# Clock2Smaller.net
KiCad netlist of a schematic drawn in EAGLE
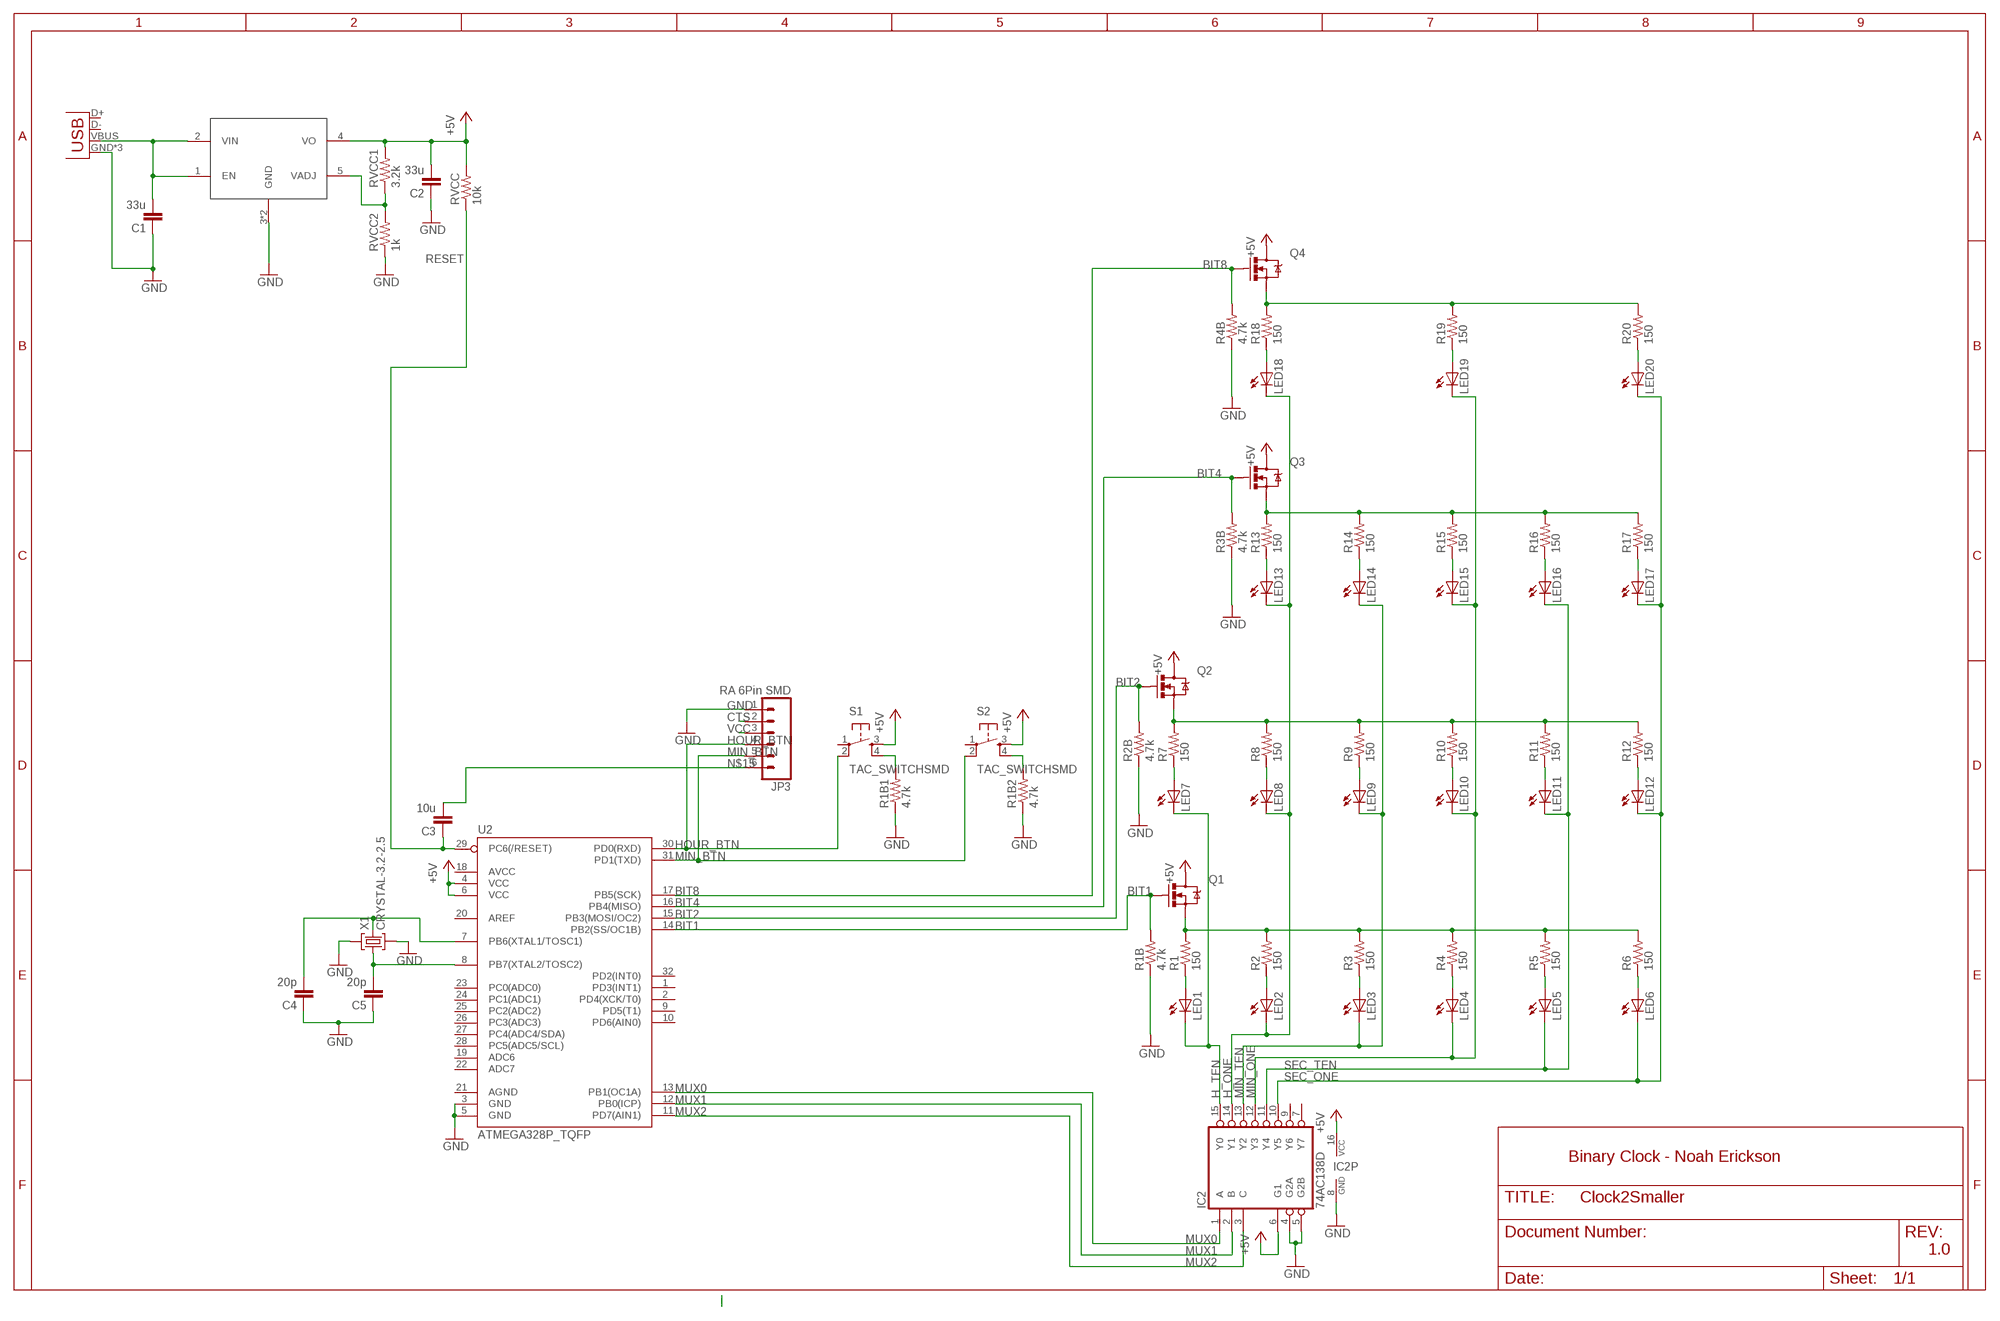
[diagram p0: schematic, sheet 1]

(export (version "E")
  (design (tool "Eeschema 10.0.6"))
  (components
    (comp (ref "C1")
      (value "33u")
      (footprint "eagle-import:C0805")
      (libsource (lib "eagle-import") (part "C-EUC0805"))
    )
    (comp (ref "C2")
      (value "33u")
      (footprint "eagle-import:C0805")
      (libsource (lib "eagle-import") (part "C-EUC0805"))
    )
    (comp (ref "C3")
      (value "10u")
      (footprint "eagle-import:C0805")
      (libsource (lib "eagle-import") (part "C-EUC0805"))
    )
    (comp (ref "C4")
      (value "20p")
      (footprint "eagle-import:C0805")
      (libsource (lib "eagle-import") (part "C-EUC0805"))
    )
    (comp (ref "C5")
      (value "20p")
      (footprint "eagle-import:C0805")
      (libsource (lib "eagle-import") (part "C-EUC0805"))
    )
    (comp (ref "IC2")
      (value "74AC138D")
      (footprint "eagle-import:SO16")
      (libsource (lib "eagle-import") (part "74138DAC"))
    )
    (comp (ref "JP1")
      (value "USB-MICROB")
      (footprint "eagle-import:USB-MICROB")
      (libsource (lib "eagle-import") (part "USB-MICROB"))
    )
    (comp (ref "JP3")
      (value "RA 6Pin SMD")
      (footprint "eagle-import:1X06-SMD")
      (libsource (lib "eagle-import") (part "M06SMD"))
    )
    (comp (ref "LED1")
      (value "LEDSML0805")
      (footprint "eagle-import:SML0805")
      (libsource (lib "eagle-import") (part "LEDSML0805"))
    )
    (comp (ref "LED2")
      (value "LEDSML0805")
      (footprint "eagle-import:SML0805")
      (libsource (lib "eagle-import") (part "LEDSML0805"))
    )
    (comp (ref "LED3")
      (value "LEDSML0805")
      (footprint "eagle-import:SML0805")
      (libsource (lib "eagle-import") (part "LEDSML0805"))
    )
    (comp (ref "LED4")
      (value "LEDSML0805")
      (footprint "eagle-import:SML0805")
      (libsource (lib "eagle-import") (part "LEDSML0805"))
    )
    (comp (ref "LED5")
      (value "LEDSML0805")
      (footprint "eagle-import:SML0805")
      (libsource (lib "eagle-import") (part "LEDSML0805"))
    )
    (comp (ref "LED6")
      (value "LEDSML0805")
      (footprint "eagle-import:SML0805")
      (libsource (lib "eagle-import") (part "LEDSML0805"))
    )
    (comp (ref "LED7")
      (value "LEDSML0805")
      (footprint "eagle-import:SML0805")
      (libsource (lib "eagle-import") (part "LEDSML0805"))
    )
    (comp (ref "LED8")
      (value "LEDSML0805")
      (footprint "eagle-import:SML0805")
      (libsource (lib "eagle-import") (part "LEDSML0805"))
    )
    (comp (ref "LED9")
      (value "LEDSML0805")
      (footprint "eagle-import:SML0805")
      (libsource (lib "eagle-import") (part "LEDSML0805"))
    )
    (comp (ref "LED10")
      (value "LEDSML0805")
      (footprint "eagle-import:SML0805")
      (libsource (lib "eagle-import") (part "LEDSML0805"))
    )
    (comp (ref "LED11")
      (value "LEDSML0805")
      (footprint "eagle-import:SML0805")
      (libsource (lib "eagle-import") (part "LEDSML0805"))
    )
    (comp (ref "LED12")
      (value "LEDSML0805")
      (footprint "eagle-import:SML0805")
      (libsource (lib "eagle-import") (part "LEDSML0805"))
    )
    (comp (ref "LED13")
      (value "LEDSML0805")
      (footprint "eagle-import:SML0805")
      (libsource (lib "eagle-import") (part "LEDSML0805"))
    )
    (comp (ref "LED14")
      (value "LEDSML0805")
      (footprint "eagle-import:SML0805")
      (libsource (lib "eagle-import") (part "LEDSML0805"))
    )
    (comp (ref "LED15")
      (value "LEDSML0805")
      (footprint "eagle-import:SML0805")
      (libsource (lib "eagle-import") (part "LEDSML0805"))
    )
    (comp (ref "LED16")
      (value "LEDSML0805")
      (footprint "eagle-import:SML0805")
      (libsource (lib "eagle-import") (part "LEDSML0805"))
    )
    (comp (ref "LED17")
      (value "LEDSML0805")
      (footprint "eagle-import:SML0805")
      (libsource (lib "eagle-import") (part "LEDSML0805"))
    )
    (comp (ref "LED18")
      (value "LEDSML0805")
      (footprint "eagle-import:SML0805")
      (libsource (lib "eagle-import") (part "LEDSML0805"))
    )
    (comp (ref "LED19")
      (value "LEDSML0805")
      (footprint "eagle-import:SML0805")
      (libsource (lib "eagle-import") (part "LEDSML0805"))
    )
    (comp (ref "LED20")
      (value "LEDSML0805")
      (footprint "eagle-import:SML0805")
      (libsource (lib "eagle-import") (part "LEDSML0805"))
    )
    (comp (ref "Q1")
      (value "MOSFET-NCHANNELBSS138")
      (footprint "eagle-import:SOT23-3")
      (libsource (lib "eagle-import") (part "MOSFET-NCHANNELBSS138"))
    )
    (comp (ref "Q2")
      (value "MOSFET-NCHANNELBSS138")
      (footprint "eagle-import:SOT23-3")
      (libsource (lib "eagle-import") (part "MOSFET-NCHANNELBSS138"))
    )
    (comp (ref "Q3")
      (value "MOSFET-NCHANNELBSS138")
      (footprint "eagle-import:SOT23-3")
      (libsource (lib "eagle-import") (part "MOSFET-NCHANNELBSS138"))
    )
    (comp (ref "Q4")
      (value "MOSFET-NCHANNELBSS138")
      (footprint "eagle-import:SOT23-3")
      (libsource (lib "eagle-import") (part "MOSFET-NCHANNELBSS138"))
    )
    (comp (ref "R1")
      (value "150")
      (footprint "eagle-import:R0805")
      (libsource (lib "eagle-import") (part "R-US_R0805"))
    )
    (comp (ref "R1B")
      (value "4.7k")
      (footprint "eagle-import:R0805")
      (libsource (lib "eagle-import") (part "R-US_R0805"))
    )
    (comp (ref "R1B1")
      (value "4.7k")
      (footprint "eagle-import:R0805")
      (libsource (lib "eagle-import") (part "R-US_R0805"))
    )
    (comp (ref "R1B2")
      (value "4.7k")
      (footprint "eagle-import:R0805")
      (libsource (lib "eagle-import") (part "R-US_R0805"))
    )
    (comp (ref "R2")
      (value "150")
      (footprint "eagle-import:R0805")
      (libsource (lib "eagle-import") (part "R-US_R0805"))
    )
    (comp (ref "R2B")
      (value "4.7k")
      (footprint "eagle-import:R0805")
      (libsource (lib "eagle-import") (part "R-US_R0805"))
    )
    (comp (ref "R3")
      (value "150")
      (footprint "eagle-import:R0805")
      (libsource (lib "eagle-import") (part "R-US_R0805"))
    )
    (comp (ref "R3B")
      (value "4.7k")
      (footprint "eagle-import:R0805")
      (libsource (lib "eagle-import") (part "R-US_R0805"))
    )
    (comp (ref "R4")
      (value "150")
      (footprint "eagle-import:R0805")
      (libsource (lib "eagle-import") (part "R-US_R0805"))
    )
    (comp (ref "R4B")
      (value "4.7k")
      (footprint "eagle-import:R0805")
      (libsource (lib "eagle-import") (part "R-US_R0805"))
    )
    (comp (ref "R5")
      (value "150")
      (footprint "eagle-import:R0805")
      (libsource (lib "eagle-import") (part "R-US_R0805"))
    )
    (comp (ref "R6")
      (value "150")
      (footprint "eagle-import:R0805")
      (libsource (lib "eagle-import") (part "R-US_R0805"))
    )
    (comp (ref "R7")
      (value "150")
      (footprint "eagle-import:R0805")
      (libsource (lib "eagle-import") (part "R-US_R0805"))
    )
    (comp (ref "R8")
      (value "150")
      (footprint "eagle-import:R0805")
      (libsource (lib "eagle-import") (part "R-US_R0805"))
    )
    (comp (ref "R9")
      (value "150")
      (footprint "eagle-import:R0805")
      (libsource (lib "eagle-import") (part "R-US_R0805"))
    )
    (comp (ref "R10")
      (value "150")
      (footprint "eagle-import:R0805")
      (libsource (lib "eagle-import") (part "R-US_R0805"))
    )
    (comp (ref "R11")
      (value "150")
      (footprint "eagle-import:R0805")
      (libsource (lib "eagle-import") (part "R-US_R0805"))
    )
    (comp (ref "R12")
      (value "150")
      (footprint "eagle-import:R0805")
      (libsource (lib "eagle-import") (part "R-US_R0805"))
    )
    (comp (ref "R13")
      (value "150")
      (footprint "eagle-import:R0805")
      (libsource (lib "eagle-import") (part "R-US_R0805"))
    )
    (comp (ref "R14")
      (value "150")
      (footprint "eagle-import:R0805")
      (libsource (lib "eagle-import") (part "R-US_R0805"))
    )
    (comp (ref "R15")
      (value "150")
      (footprint "eagle-import:R0805")
      (libsource (lib "eagle-import") (part "R-US_R0805"))
    )
    (comp (ref "R16")
      (value "150")
      (footprint "eagle-import:R0805")
      (libsource (lib "eagle-import") (part "R-US_R0805"))
    )
    (comp (ref "R17")
      (value "150")
      (footprint "eagle-import:R0805")
      (libsource (lib "eagle-import") (part "R-US_R0805"))
    )
    (comp (ref "R18")
      (value "150")
      (footprint "eagle-import:R0805")
      (libsource (lib "eagle-import") (part "R-US_R0805"))
    )
    (comp (ref "R19")
      (value "150")
      (footprint "eagle-import:R0805")
      (libsource (lib "eagle-import") (part "R-US_R0805"))
    )
    (comp (ref "R20")
      (value "150")
      (footprint "eagle-import:R0805")
      (libsource (lib "eagle-import") (part "R-US_R0805"))
    )
    (comp (ref "RVCC")
      (value "10k")
      (footprint "eagle-import:R0805")
      (libsource (lib "eagle-import") (part "R-US_R0805"))
    )
    (comp (ref "RVCC1")
      (value "3.2k")
      (footprint "eagle-import:R0805")
      (libsource (lib "eagle-import") (part "R-US_R0805"))
    )
    (comp (ref "RVCC2")
      (value "1k")
      (footprint "eagle-import:R0805")
      (libsource (lib "eagle-import") (part "R-US_R0805"))
    )
    (comp (ref "S1")
      (value "TAC_SWITCHSMD")
      (footprint "eagle-import:TACTILE-SWITCH-SMD")
      (libsource (lib "eagle-import") (part "TAC_SWITCHSMD"))
    )
    (comp (ref "S2")
      (value "TAC_SWITCHSMD")
      (footprint "eagle-import:TACTILE-SWITCH-SMD")
      (libsource (lib "eagle-import") (part "TAC_SWITCHSMD"))
    )
    (comp (ref "U$1")
      (value "TLF1963")
      (footprint "eagle-import:DPAK")
      (libsource (lib "eagle-import") (part "TLF1963"))
    )
    (comp (ref "U2")
      (value "ATMEGA328P_TQFP")
      (footprint "eagle-import:TQFP32-08")
      (libsource (lib "eagle-import") (part "ATMEGA328P_TQFP"))
    )
    (comp (ref "X1")
      (value "CRYSTAL-3.2-2.5")
      (footprint "eagle-import:CRYSTAL-3.2-2.5")
      (libsource (lib "eagle-import") (part "CRYSTAL-3.2-2.5"))
    )
  )
  (nets
    (net (code "1") (name "+5V") (class "Default")
      (node (ref "C2") (pin "2") (pinfunction "2_2") (pintype "passive"))
      (node (ref "IC2") (pin "16") (pinfunction "VCC_16") (pintype "power_in"))
      (node (ref "IC2") (pin "6") (pinfunction "G1_6") (pintype "input"))
      (node (ref "Q1") (pin "3") (pinfunction "D_3") (pintype "passive"))
      (node (ref "Q2") (pin "3") (pinfunction "D_3") (pintype "passive"))
      (node (ref "Q3") (pin "3") (pinfunction "D_3") (pintype "passive"))
      (node (ref "Q4") (pin "3") (pinfunction "D_3") (pintype "passive"))
      (node (ref "RVCC") (pin "2") (pinfunction "2_2") (pintype "passive"))
      (node (ref "RVCC1") (pin "2") (pinfunction "2_2") (pintype "passive"))
      (node (ref "S1") (pin "3") (pinfunction "3_3") (pintype "passive"))
      (node (ref "S2") (pin "3") (pinfunction "3_3") (pintype "passive"))
      (node (ref "U$1") (pin "4") (pinfunction "VO_4") (pintype "bidirectional"))
      (node (ref "U2") (pin "4") (pinfunction "VCC_4") (pintype "bidirectional"))
      (node (ref "U2") (pin "6") (pinfunction "VCC_6") (pintype "bidirectional"))
    )
    (net (code "2") (name "/BIT1") (class "Default")
      (node (ref "Q1") (pin "1") (pinfunction "G_1") (pintype "passive"))
      (node (ref "R1B") (pin "2") (pinfunction "2_2") (pintype "passive"))
      (node (ref "U2") (pin "14") (pinfunction "PB2(SS/OC1B)_14") (pintype "bidirectional"))
    )
    (net (code "3") (name "/BIT2") (class "Default")
      (node (ref "Q2") (pin "1") (pinfunction "G_1") (pintype "passive"))
      (node (ref "R2B") (pin "2") (pinfunction "2_2") (pintype "passive"))
      (node (ref "U2") (pin "15") (pinfunction "PB3(MOSI/OC2)_15") (pintype "bidirectional"))
    )
    (net (code "4") (name "/BIT4") (class "Default")
      (node (ref "Q3") (pin "1") (pinfunction "G_1") (pintype "passive"))
      (node (ref "R3B") (pin "2") (pinfunction "2_2") (pintype "passive"))
      (node (ref "U2") (pin "16") (pinfunction "PB4(MISO)_16") (pintype "bidirectional"))
    )
    (net (code "5") (name "/BIT8") (class "Default")
      (node (ref "Q4") (pin "1") (pinfunction "G_1") (pintype "passive"))
      (node (ref "R4B") (pin "2") (pinfunction "2_2") (pintype "passive"))
      (node (ref "U2") (pin "17") (pinfunction "PB5(SCK)_17") (pintype "bidirectional"))
    )
    (net (code "6") (name "/CTS") (class "Default")
      (node (ref "JP3") (pin "2") (pinfunction "2_2") (pintype "passive"))
    )
    (net (code "7") (name "/HOUR_BTN") (class "Default")
      (node (ref "JP3") (pin "4") (pinfunction "4_4") (pintype "passive"))
      (node (ref "S1") (pin "2") (pinfunction "2_2") (pintype "passive"))
      (node (ref "U2") (pin "30") (pinfunction "PD0(RXD)_30") (pintype "bidirectional"))
    )
    (net (code "8") (name "/H_ONE") (class "Default")
      (node (ref "IC2") (pin "14") (pinfunction "Y1_14") (pintype "output"))
      (node (ref "LED13") (pin "C") (pinfunction "C_C") (pintype "passive"))
      (node (ref "LED18") (pin "C") (pinfunction "C_C") (pintype "passive"))
      (node (ref "LED2") (pin "C") (pinfunction "C_C") (pintype "passive"))
      (node (ref "LED8") (pin "C") (pinfunction "C_C") (pintype "passive"))
    )
    (net (code "9") (name "/H_TEN") (class "Default")
      (node (ref "IC2") (pin "15") (pinfunction "Y0_15") (pintype "output"))
      (node (ref "LED1") (pin "C") (pinfunction "C_C") (pintype "passive"))
      (node (ref "LED7") (pin "C") (pinfunction "C_C") (pintype "passive"))
    )
    (net (code "10") (name "/MIN_BTN") (class "Default")
      (node (ref "JP3") (pin "5") (pinfunction "5_5") (pintype "passive"))
      (node (ref "S2") (pin "2") (pinfunction "2_2") (pintype "passive"))
      (node (ref "U2") (pin "31") (pinfunction "PD1(TXD)_31") (pintype "bidirectional"))
    )
    (net (code "11") (name "/MIN_ONE") (class "Default")
      (node (ref "IC2") (pin "12") (pinfunction "Y3_12") (pintype "output"))
      (node (ref "LED10") (pin "C") (pinfunction "C_C") (pintype "passive"))
      (node (ref "LED15") (pin "C") (pinfunction "C_C") (pintype "passive"))
      (node (ref "LED19") (pin "C") (pinfunction "C_C") (pintype "passive"))
      (node (ref "LED4") (pin "C") (pinfunction "C_C") (pintype "passive"))
    )
    (net (code "12") (name "/MIN_TEN") (class "Default")
      (node (ref "IC2") (pin "13") (pinfunction "Y2_13") (pintype "output"))
      (node (ref "LED14") (pin "C") (pinfunction "C_C") (pintype "passive"))
      (node (ref "LED3") (pin "C") (pinfunction "C_C") (pintype "passive"))
      (node (ref "LED9") (pin "C") (pinfunction "C_C") (pintype "passive"))
    )
    (net (code "13") (name "/MUX0") (class "Default")
      (node (ref "IC2") (pin "1") (pinfunction "A_1") (pintype "input"))
      (node (ref "U2") (pin "13") (pinfunction "PB1(OC1A)_13") (pintype "bidirectional"))
    )
    (net (code "14") (name "/MUX1") (class "Default")
      (node (ref "IC2") (pin "2") (pinfunction "B_2") (pintype "input"))
      (node (ref "U2") (pin "12") (pinfunction "PB0(ICP)_12") (pintype "bidirectional"))
    )
    (net (code "15") (name "/MUX2") (class "Default")
      (node (ref "IC2") (pin "3") (pinfunction "C_3") (pintype "input"))
      (node (ref "U2") (pin "11") (pinfunction "PD7(AIN1)_11") (pintype "bidirectional"))
    )
    (net (code "16") (name "/N$15") (class "Default")
      (node (ref "C3") (pin "2") (pinfunction "2_2") (pintype "passive"))
      (node (ref "JP3") (pin "6") (pinfunction "6_6") (pintype "passive"))
    )
    (net (code "17") (name "/RESET") (class "Default")
      (node (ref "C3") (pin "1") (pinfunction "1_1") (pintype "passive"))
      (node (ref "RVCC") (pin "1") (pinfunction "1_1") (pintype "passive"))
      (node (ref "U2") (pin "29") (pinfunction "PC6(/RESET)_29") (pintype "bidirectional"))
    )
    (net (code "18") (name "/SEC_ONE") (class "Default")
      (node (ref "IC2") (pin "10") (pinfunction "Y5_10") (pintype "output"))
      (node (ref "LED12") (pin "C") (pinfunction "C_C") (pintype "passive"))
      (node (ref "LED17") (pin "C") (pinfunction "C_C") (pintype "passive"))
      (node (ref "LED20") (pin "C") (pinfunction "C_C") (pintype "passive"))
      (node (ref "LED6") (pin "C") (pinfunction "C_C") (pintype "passive"))
    )
    (net (code "19") (name "/SEC_TEN") (class "Default")
      (node (ref "IC2") (pin "11") (pinfunction "Y4_11") (pintype "output"))
      (node (ref "LED11") (pin "C") (pinfunction "C_C") (pintype "passive"))
      (node (ref "LED16") (pin "C") (pinfunction "C_C") (pintype "passive"))
      (node (ref "LED5") (pin "C") (pinfunction "C_C") (pintype "passive"))
    )
    (net (code "20") (name "/VCC") (class "Default")
      (node (ref "JP3") (pin "3") (pinfunction "3_3") (pintype "passive"))
    )
    (net (code "21") (name "GND") (class "Default")
      (node (ref "C1") (pin "1") (pinfunction "1_1") (pintype "passive"))
      (node (ref "C2") (pin "1") (pinfunction "1_1") (pintype "passive"))
      (node (ref "C4") (pin "1") (pinfunction "1_1") (pintype "passive"))
      (node (ref "C5") (pin "1") (pinfunction "1_1") (pintype "passive"))
      (node (ref "IC2") (pin "4") (pinfunction "G2A_4") (pintype "input"))
      (node (ref "IC2") (pin "5") (pinfunction "G2B_5") (pintype "input"))
      (node (ref "IC2") (pin "8") (pinfunction "GND_8") (pintype "power_in"))
      (node (ref "JP1") (pin "GND") (pinfunction "GND_GND") (pintype "bidirectional"))
      (node (ref "JP1") (pin "MT1") (pinfunction "GND_MT1") (pintype "bidirectional"))
      (node (ref "JP1") (pin "MT2") (pinfunction "GND_MT2") (pintype "bidirectional"))
      (node (ref "JP3") (pin "1") (pinfunction "1_1") (pintype "passive"))
      (node (ref "R1B") (pin "1") (pinfunction "1_1") (pintype "passive"))
      (node (ref "R1B1") (pin "1") (pinfunction "1_1") (pintype "passive"))
      (node (ref "R1B2") (pin "1") (pinfunction "1_1") (pintype "passive"))
      (node (ref "R2B") (pin "1") (pinfunction "1_1") (pintype "passive"))
      (node (ref "R3B") (pin "1") (pinfunction "1_1") (pintype "passive"))
      (node (ref "R4B") (pin "1") (pinfunction "1_1") (pintype "passive"))
      (node (ref "RVCC2") (pin "1") (pinfunction "1_1") (pintype "passive"))
      (node (ref "U$1") (pin "3") (pinfunction "GND_3") (pintype "bidirectional"))
      (node (ref "U$1") (pin "6") (pinfunction "GND_6") (pintype "bidirectional"))
      (node (ref "U2") (pin "3") (pinfunction "GND_3") (pintype "bidirectional"))
      (node (ref "U2") (pin "5") (pinfunction "GND_5") (pintype "bidirectional"))
      (node (ref "X1") (pin "2") (pinfunction "GND_2") (pintype "passive"))
      (node (ref "X1") (pin "4") (pinfunction "GND_4") (pintype "passive"))
    )
    (net (code "22") (name "Net-(LED1-PadA)") (class "Default")
      (node (ref "LED1") (pin "A") (pinfunction "A_A") (pintype "passive"))
      (node (ref "R1") (pin "1") (pinfunction "1_1") (pintype "passive"))
    )
    (net (code "23") (name "Net-(LED2-PadA)") (class "Default")
      (node (ref "LED2") (pin "A") (pinfunction "A_A") (pintype "passive"))
      (node (ref "R2") (pin "1") (pinfunction "1_1") (pintype "passive"))
    )
    (net (code "24") (name "Net-(LED3-PadA)") (class "Default")
      (node (ref "LED3") (pin "A") (pinfunction "A_A") (pintype "passive"))
      (node (ref "R3") (pin "1") (pinfunction "1_1") (pintype "passive"))
    )
    (net (code "25") (name "Net-(LED4-PadA)") (class "Default")
      (node (ref "LED4") (pin "A") (pinfunction "A_A") (pintype "passive"))
      (node (ref "R4") (pin "1") (pinfunction "1_1") (pintype "passive"))
    )
    (net (code "26") (name "Net-(LED5-PadA)") (class "Default")
      (node (ref "LED5") (pin "A") (pinfunction "A_A") (pintype "passive"))
      (node (ref "R5") (pin "1") (pinfunction "1_1") (pintype "passive"))
    )
    (net (code "27") (name "Net-(LED6-PadA)") (class "Default")
      (node (ref "LED6") (pin "A") (pinfunction "A_A") (pintype "passive"))
      (node (ref "R6") (pin "1") (pinfunction "1_1") (pintype "passive"))
    )
    (net (code "28") (name "Net-(LED7-PadA)") (class "Default")
      (node (ref "LED7") (pin "A") (pinfunction "A_A") (pintype "passive"))
      (node (ref "R7") (pin "1") (pinfunction "1_1") (pintype "passive"))
    )
    (net (code "29") (name "Net-(LED8-PadA)") (class "Default")
      (node (ref "LED8") (pin "A") (pinfunction "A_A") (pintype "passive"))
      (node (ref "R8") (pin "1") (pinfunction "1_1") (pintype "passive"))
    )
    (net (code "30") (name "Net-(LED9-PadA)") (class "Default")
      (node (ref "LED9") (pin "A") (pinfunction "A_A") (pintype "passive"))
      (node (ref "R9") (pin "1") (pinfunction "1_1") (pintype "passive"))
    )
    (net (code "31") (name "Net-(LED10-PadA)") (class "Default")
      (node (ref "LED10") (pin "A") (pinfunction "A_A") (pintype "passive"))
      (node (ref "R10") (pin "1") (pinfunction "1_1") (pintype "passive"))
    )
    (net (code "32") (name "Net-(LED11-PadA)") (class "Default")
      (node (ref "LED11") (pin "A") (pinfunction "A_A") (pintype "passive"))
      (node (ref "R11") (pin "1") (pinfunction "1_1") (pintype "passive"))
    )
    (net (code "33") (name "Net-(LED12-PadA)") (class "Default")
      (node (ref "LED12") (pin "A") (pinfunction "A_A") (pintype "passive"))
      (node (ref "R12") (pin "1") (pinfunction "1_1") (pintype "passive"))
    )
    (net (code "34") (name "Net-(LED13-PadA)") (class "Default")
      (node (ref "LED13") (pin "A") (pinfunction "A_A") (pintype "passive"))
      (node (ref "R13") (pin "1") (pinfunction "1_1") (pintype "passive"))
    )
    (net (code "35") (name "Net-(LED14-PadA)") (class "Default")
      (node (ref "LED14") (pin "A") (pinfunction "A_A") (pintype "passive"))
      (node (ref "R14") (pin "1") (pinfunction "1_1") (pintype "passive"))
    )
    (net (code "36") (name "Net-(LED15-PadA)") (class "Default")
      (node (ref "LED15") (pin "A") (pinfunction "A_A") (pintype "passive"))
      (node (ref "R15") (pin "1") (pinfunction "1_1") (pintype "passive"))
    )
    (net (code "37") (name "Net-(LED16-PadA)") (class "Default")
      (node (ref "LED16") (pin "A") (pinfunction "A_A") (pintype "passive"))
      (node (ref "R16") (pin "1") (pinfunction "1_1") (pintype "passive"))
    )
    (net (code "38") (name "Net-(LED17-PadA)") (class "Default")
      (node (ref "LED17") (pin "A") (pinfunction "A_A") (pintype "passive"))
      (node (ref "R17") (pin "1") (pinfunction "1_1") (pintype "passive"))
    )
    (net (code "39") (name "Net-(LED18-PadA)") (class "Default")
      (node (ref "LED18") (pin "A") (pinfunction "A_A") (pintype "passive"))
      (node (ref "R18") (pin "1") (pinfunction "1_1") (pintype "passive"))
    )
    (net (code "40") (name "Net-(LED19-PadA)") (class "Default")
      (node (ref "LED19") (pin "A") (pinfunction "A_A") (pintype "passive"))
      (node (ref "R19") (pin "1") (pinfunction "1_1") (pintype "passive"))
    )
    (net (code "41") (name "Net-(LED20-PadA)") (class "Default")
      (node (ref "LED20") (pin "A") (pinfunction "A_A") (pintype "passive"))
      (node (ref "R20") (pin "1") (pinfunction "1_1") (pintype "passive"))
    )
    (net (code "42") (name "Net-(Q1-S)") (class "Default")
      (node (ref "Q1") (pin "2") (pinfunction "S_2") (pintype "passive"))
      (node (ref "R1") (pin "2") (pinfunction "2_2") (pintype "passive"))
      (node (ref "R2") (pin "2") (pinfunction "2_2") (pintype "passive"))
      (node (ref "R3") (pin "2") (pinfunction "2_2") (pintype "passive"))
      (node (ref "R4") (pin "2") (pinfunction "2_2") (pintype "passive"))
      (node (ref "R5") (pin "2") (pinfunction "2_2") (pintype "passive"))
      (node (ref "R6") (pin "2") (pinfunction "2_2") (pintype "passive"))
    )
    (net (code "43") (name "Net-(Q2-S)") (class "Default")
      (node (ref "Q2") (pin "2") (pinfunction "S_2") (pintype "passive"))
      (node (ref "R10") (pin "2") (pinfunction "2_2") (pintype "passive"))
      (node (ref "R11") (pin "2") (pinfunction "2_2") (pintype "passive"))
      (node (ref "R12") (pin "2") (pinfunction "2_2") (pintype "passive"))
      (node (ref "R7") (pin "2") (pinfunction "2_2") (pintype "passive"))
      (node (ref "R8") (pin "2") (pinfunction "2_2") (pintype "passive"))
      (node (ref "R9") (pin "2") (pinfunction "2_2") (pintype "passive"))
    )
    (net (code "44") (name "Net-(Q3-S)") (class "Default")
      (node (ref "Q3") (pin "2") (pinfunction "S_2") (pintype "passive"))
      (node (ref "R13") (pin "2") (pinfunction "2_2") (pintype "passive"))
      (node (ref "R14") (pin "2") (pinfunction "2_2") (pintype "passive"))
      (node (ref "R15") (pin "2") (pinfunction "2_2") (pintype "passive"))
      (node (ref "R16") (pin "2") (pinfunction "2_2") (pintype "passive"))
      (node (ref "R17") (pin "2") (pinfunction "2_2") (pintype "passive"))
    )
    (net (code "45") (name "Net-(Q4-S)") (class "Default")
      (node (ref "Q4") (pin "2") (pinfunction "S_2") (pintype "passive"))
      (node (ref "R18") (pin "2") (pinfunction "2_2") (pintype "passive"))
      (node (ref "R19") (pin "2") (pinfunction "2_2") (pintype "passive"))
      (node (ref "R20") (pin "2") (pinfunction "2_2") (pintype "passive"))
    )
    (net (code "46") (name "Net-(R1B1-Pad2)") (class "Default")
      (node (ref "R1B1") (pin "2") (pinfunction "2_2") (pintype "passive"))
      (node (ref "S1") (pin "4") (pinfunction "4_4") (pintype "passive"))
    )
    (net (code "47") (name "Net-(R1B2-Pad2)") (class "Default")
      (node (ref "R1B2") (pin "2") (pinfunction "2_2") (pintype "passive"))
      (node (ref "S2") (pin "4") (pinfunction "4_4") (pintype "passive"))
    )
    (net (code "48") (name "Net-(U$1-EN)") (class "Default")
      (node (ref "C1") (pin "2") (pinfunction "2_2") (pintype "passive"))
      (node (ref "JP1") (pin "VBUS") (pinfunction "VBUS_VBUS") (pintype "bidirectional"))
      (node (ref "U$1") (pin "1") (pinfunction "EN_1") (pintype "bidirectional"))
      (node (ref "U$1") (pin "2") (pinfunction "VIN_2") (pintype "bidirectional"))
    )
    (net (code "49") (name "Net-(U$1-VADJ)") (class "Default")
      (node (ref "RVCC1") (pin "1") (pinfunction "1_1") (pintype "passive"))
      (node (ref "RVCC2") (pin "2") (pinfunction "2_2") (pintype "passive"))
      (node (ref "U$1") (pin "5") (pinfunction "VADJ_5") (pintype "bidirectional"))
    )
    (net (code "50") (name "Net-(U2-PB6(XTAL1{slash}TOSC1))") (class "Default")
      (node (ref "C4") (pin "2") (pinfunction "2_2") (pintype "passive"))
      (node (ref "U2") (pin "7") (pinfunction "PB6(XTAL1/TOSC1)_7") (pintype "bidirectional"))
      (node (ref "X1") (pin "3") (pinfunction "C2_3") (pintype "passive"))
    )
    (net (code "51") (name "Net-(U2-PB7(XTAL2{slash}TOSC2))") (class "Default")
      (node (ref "C5") (pin "2") (pinfunction "2_2") (pintype "passive"))
      (node (ref "U2") (pin "8") (pinfunction "PB7(XTAL2/TOSC2)_8") (pintype "bidirectional"))
      (node (ref "X1") (pin "1") (pinfunction "C1_1") (pintype "passive"))
    )
    (net (code "52") (name "unconnected-(IC2A-Y6-Pad9)") (class "Default")
      (node (ref "IC2") (pin "9") (pinfunction "Y6_9") (pintype "output"))
    )
    (net (code "53") (name "unconnected-(IC2A-Y7-Pad7)") (class "Default")
      (node (ref "IC2") (pin "7") (pinfunction "Y7_7") (pintype "output"))
    )
    (net (code "54") (name "unconnected-(JP1-PadD+)") (class "Default")
      (node (ref "JP1") (pin "D+") (pinfunction "D+_D+") (pintype "bidirectional"))
    )
    (net (code "55") (name "unconnected-(JP1-PadD-)") (class "Default")
      (node (ref "JP1") (pin "D-") (pinfunction "D-_D-") (pintype "bidirectional"))
    )
    (net (code "56") (name "unconnected-(S1-Pad1)") (class "Default")
      (node (ref "S1") (pin "1") (pinfunction "1_1") (pintype "passive"))
    )
    (net (code "57") (name "unconnected-(S2-Pad1)") (class "Default")
      (node (ref "S2") (pin "1") (pinfunction "1_1") (pintype "passive"))
    )
    (net (code "58") (name "unconnected-(U2-ADC6-Pad19)") (class "Default")
      (node (ref "U2") (pin "19") (pinfunction "ADC6_19") (pintype "bidirectional"))
    )
    (net (code "59") (name "unconnected-(U2-ADC7-Pad22)") (class "Default")
      (node (ref "U2") (pin "22") (pinfunction "ADC7_22") (pintype "bidirectional"))
    )
    (net (code "60") (name "unconnected-(U2-AGND-Pad21)") (class "Default")
      (node (ref "U2") (pin "21") (pinfunction "AGND_21") (pintype "bidirectional"))
    )
    (net (code "61") (name "unconnected-(U2-AREF-Pad20)") (class "Default")
      (node (ref "U2") (pin "20") (pinfunction "AREF_20") (pintype "bidirectional"))
    )
    (net (code "62") (name "unconnected-(U2-AVCC-Pad18)") (class "Default")
      (node (ref "U2") (pin "18") (pinfunction "AVCC_18") (pintype "bidirectional"))
    )
    (net (code "63") (name "unconnected-(U2-PC0(ADC0)-Pad23)") (class "Default")
      (node (ref "U2") (pin "23") (pinfunction "PC0(ADC0)_23") (pintype "bidirectional"))
    )
    (net (code "64") (name "unconnected-(U2-PC1(ADC1)-Pad24)") (class "Default")
      (node (ref "U2") (pin "24") (pinfunction "PC1(ADC1)_24") (pintype "bidirectional"))
    )
    (net (code "65") (name "unconnected-(U2-PC2(ADC2)-Pad25)") (class "Default")
      (node (ref "U2") (pin "25") (pinfunction "PC2(ADC2)_25") (pintype "bidirectional"))
    )
    (net (code "66") (name "unconnected-(U2-PC3(ADC3)-Pad26)") (class "Default")
      (node (ref "U2") (pin "26") (pinfunction "PC3(ADC3)_26") (pintype "bidirectional"))
    )
    (net (code "67") (name "unconnected-(U2-PC4(ADC4{slash}SDA)-Pad27)") (class "Default")
      (node (ref "U2") (pin "27") (pinfunction "PC4(ADC4/SDA)_27") (pintype "bidirectional"))
    )
    (net (code "68") (name "unconnected-(U2-PC5(ADC5{slash}SCL)-Pad28)") (class "Default")
      (node (ref "U2") (pin "28") (pinfunction "PC5(ADC5/SCL)_28") (pintype "bidirectional"))
    )
    (net (code "69") (name "unconnected-(U2-PD2(INT0)-Pad32)") (class "Default")
      (node (ref "U2") (pin "32") (pinfunction "PD2(INT0)_32") (pintype "bidirectional"))
    )
    (net (code "70") (name "unconnected-(U2-PD3(INT1)-Pad1)") (class "Default")
      (node (ref "U2") (pin "1") (pinfunction "PD3(INT1)_1") (pintype "bidirectional"))
    )
    (net (code "71") (name "unconnected-(U2-PD4(XCK{slash}T0)-Pad2)") (class "Default")
      (node (ref "U2") (pin "2") (pinfunction "PD4(XCK/T0)_2") (pintype "bidirectional"))
    )
    (net (code "72") (name "unconnected-(U2-PD5(T1)-Pad9)") (class "Default")
      (node (ref "U2") (pin "9") (pinfunction "PD5(T1)_9") (pintype "bidirectional"))
    )
    (net (code "73") (name "unconnected-(U2-PD6(AIN0)-Pad10)") (class "Default")
      (node (ref "U2") (pin "10") (pinfunction "PD6(AIN0)_10") (pintype "bidirectional"))
    )
  )
)
